# blackfin_f_power.net
KiCad netlist of a schematic drawn in Altium Designer
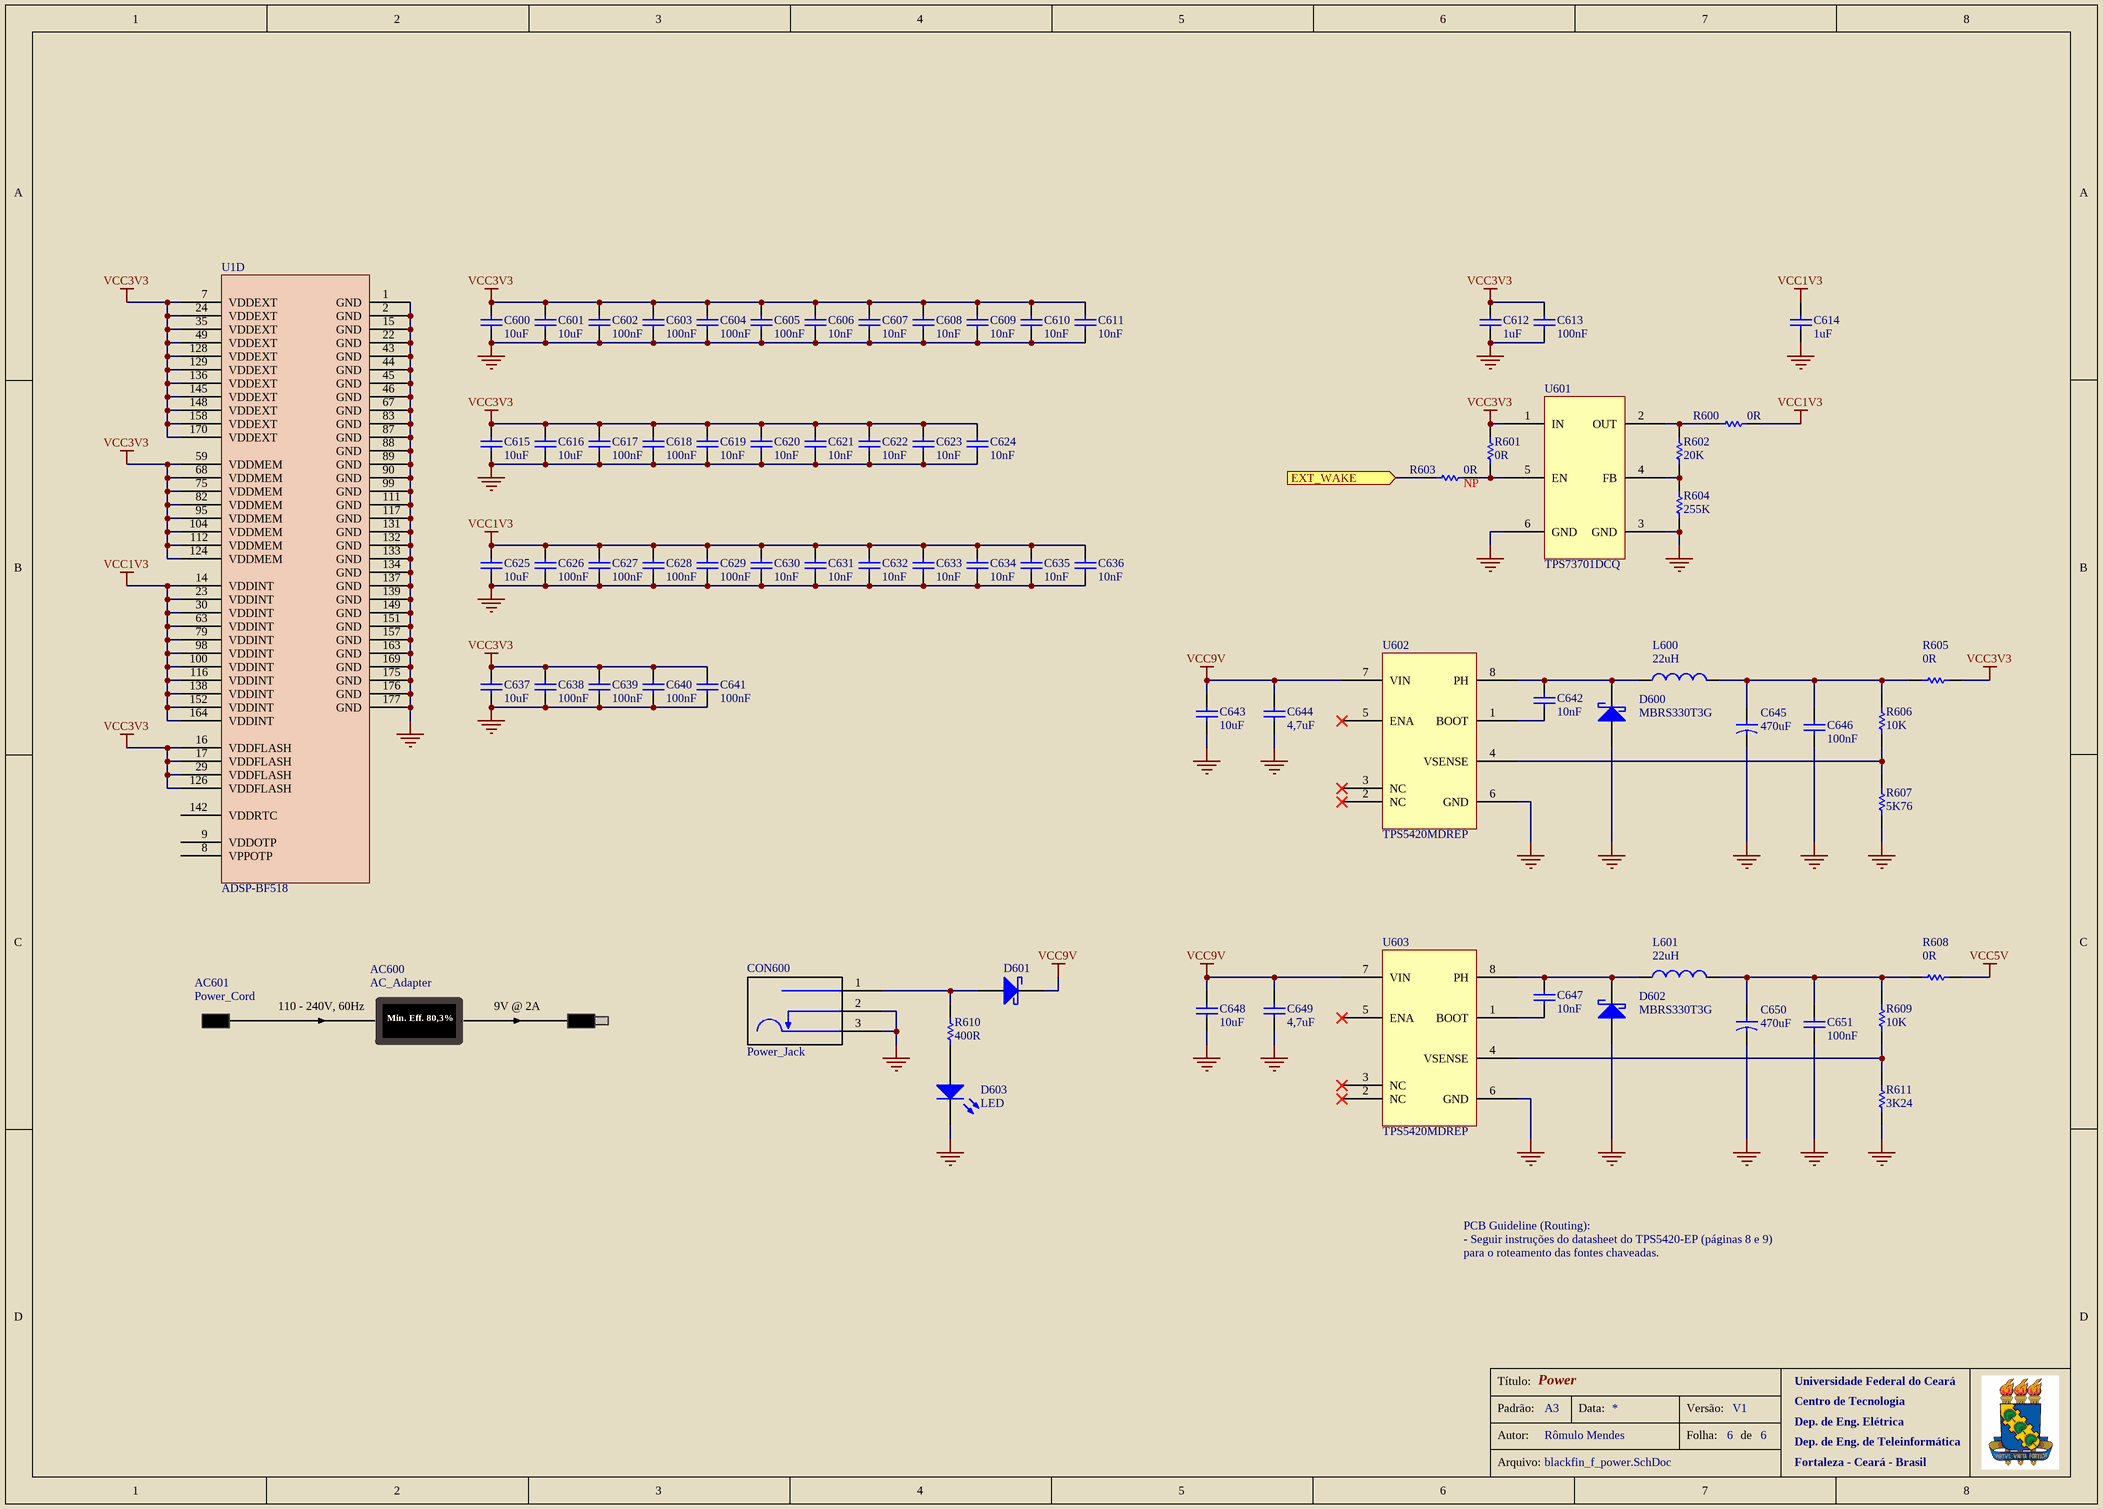
[diagram p0: blackfin_f_power.SchDoc]

(export (version "E")
  (design (tool "Eeschema 10.0.6"))
  (components
    (comp (ref "AC600")
      (value "AC_Adapter")
      (fields
        (field (name "EVENDORPART#") "552-PSA-A18U-090")
        (field (name "PART#") "PSAA18U-090-R")
        (field (name "MANUFACTURER") "Phihong")
      )
      (libsource (lib "blackfin_schlib") (part "AC_Adapter"))
    )
    (comp (ref "AC601")
      (value "Power_Cord")
      (fields
        (field (name "EVENDORPART#") "693-6009.1315")
        (field (name "PART#") "6009.1315")
        (field (name "MANUFACTURER") "Schurter")
      )
      (libsource (lib "blackfin_schlib") (part "Power_Cord"))
    )
    (comp (ref "C600")
      (value "10uF")
      (footprint "blackfin_pcblib:C_0805")
      (fields
        (field (name "EVENDORPART#") "810-C2012Y5V1C106Z")
        (field (name "MANUFACTURER") "TDK")
        (field (name "PART#") "C2012Y5V1C106Z")
      )
      (libsource (lib "blackfin_schlib") (part "Capacitor"))
    )
    (comp (ref "C601")
      (value "10uF")
      (footprint "blackfin_pcblib:C_0805")
      (fields
        (field (name "EVENDORPART#") "810-C2012Y5V1C106Z")
        (field (name "MANUFACTURER") "TDK")
        (field (name "PART#") "C2012Y5V1C106Z")
      )
      (libsource (lib "blackfin_schlib") (part "Capacitor"))
    )
    (comp (ref "C602")
      (value "100nF")
      (footprint "blackfin_pcblib:C_0603")
      (fields
        (field (name "EVENDORPART#") "81-GRM188R71E104KA01")
        (field (name "MANUFACTURER") "Murata")
        (field (name "PART#") "GRM188R71E104KA01J")
      )
      (libsource (lib "blackfin_schlib") (part "Capacitor"))
    )
    (comp (ref "C603")
      (value "100nF")
      (footprint "blackfin_pcblib:C_0603")
      (fields
        (field (name "EVENDORPART#") "81-GRM188R71E104KA01")
        (field (name "MANUFACTURER") "Murata")
        (field (name "PART#") "GRM188R71E104KA01J")
      )
      (libsource (lib "blackfin_schlib") (part "Capacitor"))
    )
    (comp (ref "C604")
      (value "100nF")
      (footprint "blackfin_pcblib:C_0603")
      (fields
        (field (name "EVENDORPART#") "81-GRM188R71E104KA01")
        (field (name "MANUFACTURER") "Murata")
        (field (name "PART#") "GRM188R71E104KA01J")
      )
      (libsource (lib "blackfin_schlib") (part "Capacitor"))
    )
    (comp (ref "C605")
      (value "100nF")
      (footprint "blackfin_pcblib:C_0603")
      (fields
        (field (name "EVENDORPART#") "81-GRM188R71E104KA01")
        (field (name "MANUFACTURER") "Murata")
        (field (name "PART#") "GRM188R71E104KA01J")
      )
      (libsource (lib "blackfin_schlib") (part "Capacitor"))
    )
    (comp (ref "C606")
      (value "10nF")
      (footprint "blackfin_pcblib:C_0603")
      (fields
        (field (name "EVENDORPART#") "77-VJ0603Y103KXAPBC")
        (field (name "MANUFACTURER") "Vishay/Vitramon")
        (field (name "PART#") "VJ0603Y103KXAPW1BC")
      )
      (libsource (lib "blackfin_schlib") (part "Capacitor"))
    )
    (comp (ref "C607")
      (value "10nF")
      (footprint "blackfin_pcblib:C_0603")
      (fields
        (field (name "EVENDORPART#") "77-VJ0603Y103KXAPBC")
        (field (name "MANUFACTURER") "Vishay/Vitramon")
        (field (name "PART#") "VJ0603Y103KXAPW1BC")
      )
      (libsource (lib "blackfin_schlib") (part "Capacitor"))
    )
    (comp (ref "C608")
      (value "10nF")
      (footprint "blackfin_pcblib:C_0603")
      (fields
        (field (name "EVENDORPART#") "77-VJ0603Y103KXAPBC")
        (field (name "MANUFACTURER") "Vishay/Vitramon")
        (field (name "PART#") "VJ0603Y103KXAPW1BC")
      )
      (libsource (lib "blackfin_schlib") (part "Capacitor"))
    )
    (comp (ref "C609")
      (value "10nF")
      (footprint "blackfin_pcblib:C_0603")
      (fields
        (field (name "EVENDORPART#") "77-VJ0603Y103KXAPBC")
        (field (name "MANUFACTURER") "Vishay/Vitramon")
        (field (name "PART#") "VJ0603Y103KXAPW1BC")
      )
      (libsource (lib "blackfin_schlib") (part "Capacitor"))
    )
    (comp (ref "C610")
      (value "10nF")
      (footprint "blackfin_pcblib:C_0603")
      (fields
        (field (name "EVENDORPART#") "77-VJ0603Y103KXAPBC")
        (field (name "MANUFACTURER") "Vishay/Vitramon")
        (field (name "PART#") "VJ0603Y103KXAPW1BC")
      )
      (libsource (lib "blackfin_schlib") (part "Capacitor"))
    )
    (comp (ref "C611")
      (value "10nF")
      (footprint "blackfin_pcblib:C_0603")
      (fields
        (field (name "EVENDORPART#") "77-VJ0603Y103KXAPBC")
        (field (name "MANUFACTURER") "Vishay/Vitramon")
        (field (name "PART#") "VJ0603Y103KXAPW1BC")
      )
      (libsource (lib "blackfin_schlib") (part "Capacitor"))
    )
    (comp (ref "C612")
      (value "1uF")
      (footprint "blackfin_pcblib:C_0603")
      (fields
        (field (name "EVENDORPART#") "81-GRM188F51E105ZA12")
        (field (name "MANUFACTURER") "Murata")
        (field (name "PART#") "GRM188F51E105ZA12D")
      )
      (libsource (lib "blackfin_schlib") (part "Capacitor"))
    )
    (comp (ref "C613")
      (value "100nF")
      (footprint "blackfin_pcblib:C_0603")
      (fields
        (field (name "EVENDORPART#") "81-GRM188R71E104KA01")
        (field (name "MANUFACTURER") "Murata")
        (field (name "PART#") "GRM188R71E104KA01J")
      )
      (libsource (lib "blackfin_schlib") (part "Capacitor"))
    )
    (comp (ref "C614")
      (value "1uF")
      (footprint "blackfin_pcblib:C_0603")
      (fields
        (field (name "EVENDORPART#") "81-GRM188F51E105ZA12")
        (field (name "MANUFACTURER") "Murata")
        (field (name "PART#") "GRM188F51E105ZA12D")
      )
      (libsource (lib "blackfin_schlib") (part "Capacitor"))
    )
    (comp (ref "C615")
      (value "10uF")
      (footprint "blackfin_pcblib:C_0805")
      (fields
        (field (name "EVENDORPART#") "810-C2012Y5V1C106Z")
        (field (name "MANUFACTURER") "TDK")
        (field (name "PART#") "C2012Y5V1C106Z")
      )
      (libsource (lib "blackfin_schlib") (part "Capacitor"))
    )
    (comp (ref "C616")
      (value "10uF")
      (footprint "blackfin_pcblib:C_0805")
      (fields
        (field (name "EVENDORPART#") "810-C2012Y5V1C106Z")
        (field (name "MANUFACTURER") "TDK")
        (field (name "PART#") "C2012Y5V1C106Z")
      )
      (libsource (lib "blackfin_schlib") (part "Capacitor"))
    )
    (comp (ref "C617")
      (value "100nF")
      (footprint "blackfin_pcblib:C_0603")
      (fields
        (field (name "EVENDORPART#") "81-GRM188R71E104KA01")
        (field (name "MANUFACTURER") "Murata")
        (field (name "PART#") "GRM188R71E104KA01J")
      )
      (libsource (lib "blackfin_schlib") (part "Capacitor"))
    )
    (comp (ref "C618")
      (value "100nF")
      (footprint "blackfin_pcblib:C_0603")
      (fields
        (field (name "EVENDORPART#") "81-GRM188R71E104KA01")
        (field (name "MANUFACTURER") "Murata")
        (field (name "PART#") "GRM188R71E104KA01J")
      )
      (libsource (lib "blackfin_schlib") (part "Capacitor"))
    )
    (comp (ref "C619")
      (value "10nF")
      (footprint "blackfin_pcblib:C_0603")
      (fields
        (field (name "EVENDORPART#") "77-VJ0603Y103KXAPBC")
        (field (name "MANUFACTURER") "Vishay/Vitramon")
        (field (name "PART#") "VJ0603Y103KXAPW1BC")
      )
      (libsource (lib "blackfin_schlib") (part "Capacitor"))
    )
    (comp (ref "C620")
      (value "10nF")
      (footprint "blackfin_pcblib:C_0603")
      (fields
        (field (name "EVENDORPART#") "77-VJ0603Y103KXAPBC")
        (field (name "MANUFACTURER") "Vishay/Vitramon")
        (field (name "PART#") "VJ0603Y103KXAPW1BC")
      )
      (libsource (lib "blackfin_schlib") (part "Capacitor"))
    )
    (comp (ref "C621")
      (value "10nF")
      (footprint "blackfin_pcblib:C_0603")
      (fields
        (field (name "EVENDORPART#") "77-VJ0603Y103KXAPBC")
        (field (name "MANUFACTURER") "Vishay/Vitramon")
        (field (name "PART#") "VJ0603Y103KXAPW1BC")
      )
      (libsource (lib "blackfin_schlib") (part "Capacitor"))
    )
    (comp (ref "C622")
      (value "10nF")
      (footprint "blackfin_pcblib:C_0603")
      (fields
        (field (name "EVENDORPART#") "77-VJ0603Y103KXAPBC")
        (field (name "MANUFACTURER") "Vishay/Vitramon")
        (field (name "PART#") "VJ0603Y103KXAPW1BC")
      )
      (libsource (lib "blackfin_schlib") (part "Capacitor"))
    )
    (comp (ref "C623")
      (value "10nF")
      (footprint "blackfin_pcblib:C_0603")
      (fields
        (field (name "EVENDORPART#") "77-VJ0603Y103KXAPBC")
        (field (name "MANUFACTURER") "Vishay/Vitramon")
        (field (name "PART#") "VJ0603Y103KXAPW1BC")
      )
      (libsource (lib "blackfin_schlib") (part "Capacitor"))
    )
    (comp (ref "C624")
      (value "10nF")
      (footprint "blackfin_pcblib:C_0603")
      (fields
        (field (name "EVENDORPART#") "77-VJ0603Y103KXAPBC")
        (field (name "MANUFACTURER") "Vishay/Vitramon")
        (field (name "PART#") "VJ0603Y103KXAPW1BC")
      )
      (libsource (lib "blackfin_schlib") (part "Capacitor"))
    )
    (comp (ref "C625")
      (value "10uF")
      (footprint "blackfin_pcblib:C_0805")
      (fields
        (field (name "EVENDORPART#") "810-C2012Y5V1C106Z")
        (field (name "MANUFACTURER") "TDK")
        (field (name "PART#") "C2012Y5V1C106Z")
      )
      (libsource (lib "blackfin_schlib") (part "Capacitor"))
    )
    (comp (ref "C626")
      (value "100nF")
      (footprint "blackfin_pcblib:C_0603")
      (fields
        (field (name "EVENDORPART#") "81-GRM188R71E104KA01")
        (field (name "MANUFACTURER") "Murata")
        (field (name "PART#") "GRM188R71E104KA01J")
      )
      (libsource (lib "blackfin_schlib") (part "Capacitor"))
    )
    (comp (ref "C627")
      (value "100nF")
      (footprint "blackfin_pcblib:C_0603")
      (fields
        (field (name "EVENDORPART#") "81-GRM188R71E104KA01")
        (field (name "MANUFACTURER") "Murata")
        (field (name "PART#") "GRM188R71E104KA01J")
      )
      (libsource (lib "blackfin_schlib") (part "Capacitor"))
    )
    (comp (ref "C628")
      (value "100nF")
      (footprint "blackfin_pcblib:C_0603")
      (fields
        (field (name "EVENDORPART#") "81-GRM188R71E104KA01")
        (field (name "MANUFACTURER") "Murata")
        (field (name "PART#") "GRM188R71E104KA01J")
      )
      (libsource (lib "blackfin_schlib") (part "Capacitor"))
    )
    (comp (ref "C629")
      (value "100nF")
      (footprint "blackfin_pcblib:C_0603")
      (fields
        (field (name "EVENDORPART#") "81-GRM188R71E104KA01")
        (field (name "MANUFACTURER") "Murata")
        (field (name "PART#") "GRM188R71E104KA01J")
      )
      (libsource (lib "blackfin_schlib") (part "Capacitor"))
    )
    (comp (ref "C630")
      (value "10nF")
      (footprint "blackfin_pcblib:C_0603")
      (fields
        (field (name "EVENDORPART#") "77-VJ0603Y103KXAPBC")
        (field (name "MANUFACTURER") "Vishay/Vitramon")
        (field (name "PART#") "VJ0603Y103KXAPW1BC")
      )
      (libsource (lib "blackfin_schlib") (part "Capacitor"))
    )
    (comp (ref "C631")
      (value "10nF")
      (footprint "blackfin_pcblib:C_0603")
      (fields
        (field (name "EVENDORPART#") "77-VJ0603Y103KXAPBC")
        (field (name "MANUFACTURER") "Vishay/Vitramon")
        (field (name "PART#") "VJ0603Y103KXAPW1BC")
      )
      (libsource (lib "blackfin_schlib") (part "Capacitor"))
    )
    (comp (ref "C632")
      (value "10nF")
      (footprint "blackfin_pcblib:C_0603")
      (fields
        (field (name "EVENDORPART#") "77-VJ0603Y103KXAPBC")
        (field (name "MANUFACTURER") "Vishay/Vitramon")
        (field (name "PART#") "VJ0603Y103KXAPW1BC")
      )
      (libsource (lib "blackfin_schlib") (part "Capacitor"))
    )
    (comp (ref "C633")
      (value "10nF")
      (footprint "blackfin_pcblib:C_0603")
      (fields
        (field (name "EVENDORPART#") "77-VJ0603Y103KXAPBC")
        (field (name "MANUFACTURER") "Vishay/Vitramon")
        (field (name "PART#") "VJ0603Y103KXAPW1BC")
      )
      (libsource (lib "blackfin_schlib") (part "Capacitor"))
    )
    (comp (ref "C634")
      (value "10nF")
      (footprint "blackfin_pcblib:C_0603")
      (fields
        (field (name "EVENDORPART#") "77-VJ0603Y103KXAPBC")
        (field (name "MANUFACTURER") "Vishay/Vitramon")
        (field (name "PART#") "VJ0603Y103KXAPW1BC")
      )
      (libsource (lib "blackfin_schlib") (part "Capacitor"))
    )
    (comp (ref "C635")
      (value "10nF")
      (footprint "blackfin_pcblib:C_0603")
      (fields
        (field (name "EVENDORPART#") "77-VJ0603Y103KXAPBC")
        (field (name "MANUFACTURER") "Vishay/Vitramon")
        (field (name "PART#") "VJ0603Y103KXAPW1BC")
      )
      (libsource (lib "blackfin_schlib") (part "Capacitor"))
    )
    (comp (ref "C636")
      (value "10nF")
      (footprint "blackfin_pcblib:C_0603")
      (fields
        (field (name "EVENDORPART#") "77-VJ0603Y103KXAPBC")
        (field (name "MANUFACTURER") "Vishay/Vitramon")
        (field (name "PART#") "VJ0603Y103KXAPW1BC")
      )
      (libsource (lib "blackfin_schlib") (part "Capacitor"))
    )
    (comp (ref "C637")
      (value "10uF")
      (footprint "blackfin_pcblib:C_0805")
      (fields
        (field (name "EVENDORPART#") "810-C2012Y5V1C106Z")
        (field (name "MANUFACTURER") "TDK")
        (field (name "PART#") "C2012Y5V1C106Z")
      )
      (libsource (lib "blackfin_schlib") (part "Capacitor"))
    )
    (comp (ref "C638")
      (value "100nF")
      (footprint "blackfin_pcblib:C_0603")
      (fields
        (field (name "EVENDORPART#") "81-GRM188R71E104KA01")
        (field (name "MANUFACTURER") "Murata")
        (field (name "PART#") "GRM188R71E104KA01J")
      )
      (libsource (lib "blackfin_schlib") (part "Capacitor"))
    )
    (comp (ref "C639")
      (value "100nF")
      (footprint "blackfin_pcblib:C_0603")
      (fields
        (field (name "EVENDORPART#") "81-GRM188R71E104KA01")
        (field (name "MANUFACTURER") "Murata")
        (field (name "PART#") "GRM188R71E104KA01J")
      )
      (libsource (lib "blackfin_schlib") (part "Capacitor"))
    )
    (comp (ref "C640")
      (value "100nF")
      (footprint "blackfin_pcblib:C_0603")
      (fields
        (field (name "EVENDORPART#") "81-GRM188R71E104KA01")
        (field (name "MANUFACTURER") "Murata")
        (field (name "PART#") "GRM188R71E104KA01J")
      )
      (libsource (lib "blackfin_schlib") (part "Capacitor"))
    )
    (comp (ref "C641")
      (value "100nF")
      (footprint "blackfin_pcblib:C_0603")
      (fields
        (field (name "EVENDORPART#") "81-GRM188R71E104KA01")
        (field (name "MANUFACTURER") "Murata")
        (field (name "PART#") "GRM188R71E104KA01J")
      )
      (libsource (lib "blackfin_schlib") (part "Capacitor"))
    )
    (comp (ref "C642")
      (value "10nF")
      (footprint "blackfin_pcblib:C_0805")
      (fields
        (field (name "EVENDORPART#") "81-GRM216R71H103JA1D")
        (field (name "MANUFACTURER") "Murata")
        (field (name "PART#") "GRM216R71H103JA01D")
      )
      (libsource (lib "blackfin_schlib") (part "Capacitor"))
    )
    (comp (ref "C643")
      (value "10uF")
      (footprint "blackfin_pcblib:C_0805")
      (fields
        (field (name "EVENDORPART#") "810-C2012X5R1C106M")
        (field (name "MANUFACTURER") "TDK")
        (field (name "PART#") "C2012X5R1C106M")
      )
      (libsource (lib "blackfin_schlib") (part "Capacitor"))
    )
    (comp (ref "C644")
      (value "4,7uF")
      (footprint "blackfin_pcblib:C_0805")
      (fields
        (field (name "EVENDORPART#") "81-GRM21BR61C475KA8L")
        (field (name "MANUFACTURER") "Murata")
        (field (name "PART#") "GRM21BR61C475KA88L")
      )
      (libsource (lib "blackfin_schlib") (part "Capacitor"))
    )
    (comp (ref "C645")
      (value "470uF")
      (footprint "blackfin_pcblib:C_Case_Y")
      (fields
        (field (name "EVENDORPART#") "80-T520Y477M6ATE15")
        (field (name "PART#") "T520Y477M006ATE015")
        (field (name "MANUFACTURER") "Kemet")
      )
      (libsource (lib "blackfin_schlib") (part "Capacitor_Pol"))
    )
    (comp (ref "C646")
      (value "100nF")
      (footprint "blackfin_pcblib:C_0603")
      (fields
        (field (name "EVENDORPART#") "81-GRM188R71E104KA01")
        (field (name "MANUFACTURER") "Murata")
        (field (name "PART#") "GRM188R71E104KA01J")
      )
      (libsource (lib "blackfin_schlib") (part "Capacitor"))
    )
    (comp (ref "C647")
      (value "10nF")
      (footprint "blackfin_pcblib:C_0805")
      (fields
        (field (name "EVENDORPART#") "81-GRM216R71H103JA1D")
        (field (name "MANUFACTURER") "Murata")
        (field (name "PART#") "GRM216R71H103JA01D")
      )
      (libsource (lib "blackfin_schlib") (part "Capacitor"))
    )
    (comp (ref "C648")
      (value "10uF")
      (footprint "blackfin_pcblib:C_0805")
      (fields
        (field (name "EVENDORPART#") "810-C2012X5R1C106M")
        (field (name "MANUFACTURER") "TDK")
        (field (name "PART#") "C2012X5R1C106M")
      )
      (libsource (lib "blackfin_schlib") (part "Capacitor"))
    )
    (comp (ref "C649")
      (value "4,7uF")
      (footprint "blackfin_pcblib:C_0805")
      (fields
        (field (name "EVENDORPART#") "81-GRM21BR61C475KA8L")
        (field (name "MANUFACTURER") "Murata")
        (field (name "PART#") "GRM21BR61C475KA88L")
      )
      (libsource (lib "blackfin_schlib") (part "Capacitor"))
    )
    (comp (ref "C650")
      (value "470uF")
      (footprint "blackfin_pcblib:C_Case_Y")
      (fields
        (field (name "EVENDORPART#") "80-T520Y477M6ATE15")
        (field (name "PART#") "T520Y477M006ATE015")
        (field (name "MANUFACTURER") "Kemet")
      )
      (libsource (lib "blackfin_schlib") (part "Capacitor_Pol"))
    )
    (comp (ref "C651")
      (value "100nF")
      (footprint "blackfin_pcblib:C_0603")
      (fields
        (field (name "EVENDORPART#") "81-GRM188R71E104KA01")
        (field (name "MANUFACTURER") "Murata")
        (field (name "PART#") "GRM188R71E104KA01J")
      )
      (libsource (lib "blackfin_schlib") (part "Capacitor"))
    )
    (comp (ref "CON600")
      (value "Power_Jack")
      (footprint "blackfin_pcblib:Power_Jack")
      (fields (field (name "EVENDORPART#") "163-179PH-EX") (field (name "MANUFACTURER") "Kobiconn"))
      (libsource (lib "blackfin_schlib") (part "Power_Jack"))
    )
    (comp (ref "D600")
      (value "MBRS330T3G")
      (footprint "blackfin_pcblib:Case_430")
      (fields (field (name "EVENDORPART#") "863-MBRS330T3G") (field (name "MANUFACTURER") "ON Semiconductor"))
      (libsource (lib "blackfin_schlib") (part "Schottky_Diode"))
    )
    (comp (ref "D601")
      (value "Schottky_Diode")
      (footprint "blackfin_pcblib:Case_430")
      (fields
        (field (name "EVENDORPART#") "863-MBRS330T3G")
        (field (name "PART#") "MBRS330T3G")
        (field (name "MANUFACTURER") "ON Semiconductor")
      )
      (libsource (lib "blackfin_schlib") (part "Schottky_Diode"))
    )
    (comp (ref "D602")
      (value "MBRS330T3G")
      (footprint "blackfin_pcblib:Case_430")
      (fields (field (name "EVENDORPART#") "863-MBRS330T3G") (field (name "MANUFACTURER") "ON Semiconductor"))
      (libsource (lib "blackfin_schlib") (part "Schottky_Diode"))
    )
    (comp (ref "D603")
      (value "LED")
      (footprint "blackfin_pcblib:LED_0603")
      (description "Red LED")
      (fields (field (name "EVENDORPART#") "638-QTLP600C2TR") (field (name "MANUFACTURER") "Everlight"))
      (libsource (lib "blackfin_schlib") (part "LED"))
    )
    (comp (ref "L600")
      (value "22uH")
      (footprint "blackfin_pcblib:Inductor_22uH")
      (fields
        (field (name "EVENDORPART#") "710-744066220")
        (field (name "MANUFACTURER") "Wurth Electronics")
        (field (name "PART#") "744066220")
      )
      (libsource (lib "blackfin_schlib") (part "Inductor"))
    )
    (comp (ref "L601")
      (value "22uH")
      (footprint "blackfin_pcblib:Inductor_22uH")
      (fields
        (field (name "EVENDORPART#") "710-744066220")
        (field (name "MANUFACTURER") "Wurth Electronics")
        (field (name "PART#") "744066220")
      )
      (libsource (lib "blackfin_schlib") (part "Inductor"))
    )
    (comp (ref "R600")
      (value "0R")
      (footprint "blackfin_pcblib:R_0603")
      (fields
        (field (name "EVENDORPART#") "71-CRCW06030000Z0EB")
        (field (name "PART#") "CRCW06030000Z0EB")
        (field (name "MANUFACTURER") "Vishay/Dale")
      )
      (libsource (lib "blackfin_schlib") (part "Resistor"))
    )
    (comp (ref "R601")
      (value "0R")
      (footprint "blackfin_pcblib:R_0603")
      (fields
        (field (name "EVENDORPART#") "71-CRCW06030000Z0EB")
        (field (name "PART#") "CRCW06030000Z0EB")
        (field (name "MANUFACTURER") "Vishay/Dale")
      )
      (libsource (lib "blackfin_schlib") (part "Resistor"))
    )
    (comp (ref "R602")
      (value "20K")
      (footprint "blackfin_pcblib:R_0603")
      (fields
        (field (name "EVENDORPART#") "71-CRCW0603J-20K-E3")
        (field (name "PART#") "CRCW060320K0JNEA")
        (field (name "MANUFACTURER") "Vishay/Dale")
      )
      (libsource (lib "blackfin_schlib") (part "Resistor"))
    )
    (comp (ref "R603")
      (value "0R")
      (footprint "blackfin_pcblib:R_0603")
      (fields
        (field (name "EVENDORPART#") "71-CRCW06030000Z0EB")
        (field (name "PART#") "CRCW06030000Z0EB")
        (field (name "MANUFACTURER") "Vishay/Dale")
      )
      (libsource (lib "blackfin_schlib") (part "Resistor"))
    )
    (comp (ref "R604")
      (value "255K")
      (footprint "blackfin_pcblib:R_0603")
      (fields
        (field (name "EVENDORPART#") "71-CRCW0603-255K-E3")
        (field (name "PART#") "CRCW0603255KFKEA")
        (field (name "MANUFACTURER") "Vishay/Dale")
      )
      (libsource (lib "blackfin_schlib") (part "Resistor"))
    )
    (comp (ref "R605")
      (value "0R")
      (footprint "blackfin_pcblib:R_2512")
      (fields
        (field (name "EVENDORPART#") "71-CRCW2512-0-E3")
        (field (name "PART#") "CRCW25120000Z0EG")
        (field (name "MANUFACTURER") "Vishay/Dale")
      )
      (libsource (lib "blackfin_schlib") (part "Resistor"))
    )
    (comp (ref "R606")
      (value "10K")
      (footprint "blackfin_pcblib:R_0603")
      (fields
        (field (name "EVENDORPART#") "71-CRCW0603-10K-E3")
        (field (name "PART#") "CRCW060310K0FKEA")
        (field (name "MANUFACTURER") "Vishay/Dale")
      )
      (libsource (lib "blackfin_schlib") (part "Resistor"))
    )
    (comp (ref "R607")
      (value "5K76")
      (footprint "blackfin_pcblib:R_0603")
      (fields
        (field (name "EVENDORPART#") "660-RK73H1JTTDD5761F")
        (field (name "PART#") "RK73H1JTTDD5761F")
        (field (name "MANUFACTURER") "KOA Speer")
      )
      (libsource (lib "blackfin_schlib") (part "Resistor"))
    )
    (comp (ref "R608")
      (value "0R")
      (footprint "blackfin_pcblib:R_2512")
      (fields
        (field (name "EVENDORPART#") "71-CRCW2512-0-E3")
        (field (name "PART#") "CRCW25120000Z0EG")
        (field (name "MANUFACTURER") "Vishay/Dale")
      )
      (libsource (lib "blackfin_schlib") (part "Resistor"))
    )
    (comp (ref "R609")
      (value "10K")
      (footprint "blackfin_pcblib:R_0603")
      (fields
        (field (name "EVENDORPART#") "71-CRCW0603-10K-E3")
        (field (name "PART#") "CRCW060310K0FKEA")
        (field (name "MANUFACTURER") "Vishay/Dale")
      )
      (libsource (lib "blackfin_schlib") (part "Resistor"))
    )
    (comp (ref "R610")
      (value "400R")
      (footprint "blackfin_pcblib:R_1206")
      (fields
        (field (name "EVENDORPART#") "71-CRCW1206390RJNEB")
        (field (name "PART#") "CRCW1206390RJNEB")
        (field (name "MANUFACTURER") "Vishay/Dale")
      )
      (libsource (lib "blackfin_schlib") (part "Resistor"))
    )
    (comp (ref "R611")
      (value "3K24")
      (footprint "blackfin_pcblib:R_0603")
      (fields
        (field (name "EVENDORPART#") "71-CRCW0603-3.24K-E3")
        (field (name "PART#") "CRCW06033K24FKEA")
        (field (name "MANUFACTURER") "Vishay/Dale")
      )
      (libsource (lib "blackfin_schlib") (part "Resistor"))
    )
    (comp (ref "U1")
      (value "ADSP-BF518")
      (footprint "blackfin_pcblib:LQFP-176")
      (fields (field (name "EVENDORPART#") "ADSP-BF518BSWZ-4") (field (name "MANUFACTURER") "Analog Devices"))
      (libsource (lib "blackfin_schlib") (part "ADSP-BF518"))
    )
    (comp (ref "U601")
      (value "TPS73701DCQ")
      (footprint "blackfin_pcblib:SOT-223")
      (fields
        (field (name "EVENDORPART#") "595-TPS73701DCQ")
        (field (name "MANUFACTURER") "Texas Instruments")
      )
      (libsource (lib "blackfin_schlib") (part "TPS73701DCQ"))
    )
    (comp (ref "U602")
      (value "TPS5420MDREP")
      (footprint "blackfin_pcblib:SOIC-8 (TPS5420MDREP)")
      (fields
        (field (name "EVENDORPART#") "595-TPS5420MDREP")
        (field (name "MANUFACTURER") "Texas Instruments")
      )
      (libsource (lib "blackfin_schlib") (part "TPS5420MDREP"))
    )
    (comp (ref "U603")
      (value "TPS5420MDREP")
      (footprint "blackfin_pcblib:SOIC-8 (TPS5420MDREP)")
      (fields
        (field (name "EVENDORPART#") "595-TPS5420MDREP")
        (field (name "MANUFACTURER") "Texas Instruments")
      )
      (libsource (lib "blackfin_schlib") (part "TPS5420MDREP"))
    )
  )
  (nets
    (net (code "1") (name "/EXT_WAKE") (class "Default")
      (node (ref "R603") (pin "1") (pinfunction "1_1") (pintype "passive"))
    )
    (net (code "2") (name "GND") (class "Default")
      (node (ref "C600") (pin "1") (pinfunction "1_1") (pintype "passive"))
      (node (ref "C601") (pin "1") (pinfunction "1_1") (pintype "passive"))
      (node (ref "C602") (pin "1") (pinfunction "1_1") (pintype "passive"))
      (node (ref "C603") (pin "1") (pinfunction "1_1") (pintype "passive"))
      (node (ref "C604") (pin "1") (pinfunction "1_1") (pintype "passive"))
      (node (ref "C605") (pin "1") (pinfunction "1_1") (pintype "passive"))
      (node (ref "C606") (pin "1") (pinfunction "1_1") (pintype "passive"))
      (node (ref "C607") (pin "1") (pinfunction "1_1") (pintype "passive"))
      (node (ref "C608") (pin "1") (pinfunction "1_1") (pintype "passive"))
      (node (ref "C609") (pin "1") (pinfunction "1_1") (pintype "passive"))
      (node (ref "C610") (pin "1") (pinfunction "1_1") (pintype "passive"))
      (node (ref "C611") (pin "1") (pinfunction "1_1") (pintype "passive"))
      (node (ref "C612") (pin "1") (pinfunction "1_1") (pintype "passive"))
      (node (ref "C613") (pin "1") (pinfunction "1_1") (pintype "passive"))
      (node (ref "C614") (pin "1") (pinfunction "1_1") (pintype "passive"))
      (node (ref "C615") (pin "1") (pinfunction "1_1") (pintype "passive"))
      (node (ref "C616") (pin "1") (pinfunction "1_1") (pintype "passive"))
      (node (ref "C617") (pin "1") (pinfunction "1_1") (pintype "passive"))
      (node (ref "C618") (pin "1") (pinfunction "1_1") (pintype "passive"))
      (node (ref "C619") (pin "1") (pinfunction "1_1") (pintype "passive"))
      (node (ref "C620") (pin "1") (pinfunction "1_1") (pintype "passive"))
      (node (ref "C621") (pin "1") (pinfunction "1_1") (pintype "passive"))
      (node (ref "C622") (pin "1") (pinfunction "1_1") (pintype "passive"))
      (node (ref "C623") (pin "1") (pinfunction "1_1") (pintype "passive"))
      (node (ref "C624") (pin "1") (pinfunction "1_1") (pintype "passive"))
      (node (ref "C625") (pin "1") (pinfunction "1_1") (pintype "passive"))
      (node (ref "C626") (pin "1") (pinfunction "1_1") (pintype "passive"))
      (node (ref "C627") (pin "1") (pinfunction "1_1") (pintype "passive"))
      (node (ref "C628") (pin "1") (pinfunction "1_1") (pintype "passive"))
      (node (ref "C629") (pin "1") (pinfunction "1_1") (pintype "passive"))
      (node (ref "C630") (pin "1") (pinfunction "1_1") (pintype "passive"))
      (node (ref "C631") (pin "1") (pinfunction "1_1") (pintype "passive"))
      (node (ref "C632") (pin "1") (pinfunction "1_1") (pintype "passive"))
      (node (ref "C633") (pin "1") (pinfunction "1_1") (pintype "passive"))
      (node (ref "C634") (pin "1") (pinfunction "1_1") (pintype "passive"))
      (node (ref "C635") (pin "1") (pinfunction "1_1") (pintype "passive"))
      (node (ref "C636") (pin "1") (pinfunction "1_1") (pintype "passive"))
      (node (ref "C637") (pin "1") (pinfunction "1_1") (pintype "passive"))
      (node (ref "C638") (pin "1") (pinfunction "1_1") (pintype "passive"))
      (node (ref "C639") (pin "1") (pinfunction "1_1") (pintype "passive"))
      (node (ref "C640") (pin "1") (pinfunction "1_1") (pintype "passive"))
      (node (ref "C641") (pin "1") (pinfunction "1_1") (pintype "passive"))
      (node (ref "C643") (pin "1") (pinfunction "1_1") (pintype "passive"))
      (node (ref "C644") (pin "1") (pinfunction "1_1") (pintype "passive"))
      (node (ref "C645") (pin "2") (pinfunction "2_2") (pintype "passive"))
      (node (ref "C646") (pin "1") (pinfunction "1_1") (pintype "passive"))
      (node (ref "C648") (pin "1") (pinfunction "1_1") (pintype "passive"))
      (node (ref "C649") (pin "1") (pinfunction "1_1") (pintype "passive"))
      (node (ref "C650") (pin "2") (pinfunction "2_2") (pintype "passive"))
      (node (ref "C651") (pin "1") (pinfunction "1_1") (pintype "passive"))
      (node (ref "CON600") (pin "2") (pinfunction "2_2") (pintype "passive"))
      (node (ref "CON600") (pin "3") (pinfunction "3_3") (pintype "passive"))
      (node (ref "D600") (pin "1") (pinfunction "A_1") (pintype "passive"))
      (node (ref "D602") (pin "1") (pinfunction "A_1") (pintype "passive"))
      (node (ref "D603") (pin "2") (pinfunction "K_2") (pintype "passive"))
      (node (ref "R604") (pin "1") (pinfunction "1_1") (pintype "passive"))
      (node (ref "R607") (pin "1") (pinfunction "1_1") (pintype "passive"))
      (node (ref "R611") (pin "1") (pinfunction "1_1") (pintype "passive"))
      (node (ref "U1") (pin "1") (pinfunction "GND_1") (pintype "passive"))
      (node (ref "U1") (pin "111") (pinfunction "GND_111") (pintype "passive"))
      (node (ref "U1") (pin "117") (pinfunction "GND_117") (pintype "passive"))
      (node (ref "U1") (pin "131") (pinfunction "GND_131") (pintype "passive"))
      (node (ref "U1") (pin "132") (pinfunction "GND_132") (pintype "passive"))
      (node (ref "U1") (pin "133") (pinfunction "GND_133") (pintype "passive"))
      (node (ref "U1") (pin "134") (pinfunction "GND_134") (pintype "passive"))
      (node (ref "U1") (pin "137") (pinfunction "GND_137") (pintype "passive"))
      (node (ref "U1") (pin "139") (pinfunction "GND_139") (pintype "passive"))
      (node (ref "U1") (pin "149") (pinfunction "GND_149") (pintype "passive"))
      (node (ref "U1") (pin "15") (pinfunction "GND_15") (pintype "passive"))
      (node (ref "U1") (pin "151") (pinfunction "GND_151") (pintype "passive"))
      (node (ref "U1") (pin "157") (pinfunction "GND_157") (pintype "passive"))
      (node (ref "U1") (pin "163") (pinfunction "GND_163") (pintype "passive"))
      (node (ref "U1") (pin "169") (pinfunction "GND_169") (pintype "passive"))
      (node (ref "U1") (pin "175") (pinfunction "GND_175") (pintype "passive"))
      (node (ref "U1") (pin "176") (pinfunction "GND_176") (pintype "passive"))
      (node (ref "U1") (pin "177") (pinfunction "GND_177") (pintype "passive"))
      (node (ref "U1") (pin "2") (pinfunction "GND_2") (pintype "passive"))
      (node (ref "U1") (pin "22") (pinfunction "GND_22") (pintype "passive"))
      (node (ref "U1") (pin "43") (pinfunction "GND_43") (pintype "passive"))
      (node (ref "U1") (pin "44") (pinfunction "GND_44") (pintype "passive"))
      (node (ref "U1") (pin "45") (pinfunction "GND_45") (pintype "passive"))
      (node (ref "U1") (pin "46") (pinfunction "GND_46") (pintype "passive"))
      (node (ref "U1") (pin "67") (pinfunction "GND_67") (pintype "passive"))
      (node (ref "U1") (pin "83") (pinfunction "GND_83") (pintype "passive"))
      (node (ref "U1") (pin "87") (pinfunction "GND_87") (pintype "passive"))
      (node (ref "U1") (pin "88") (pinfunction "GND_88") (pintype "passive"))
      (node (ref "U1") (pin "89") (pinfunction "GND_89") (pintype "passive"))
      (node (ref "U1") (pin "90") (pinfunction "GND_90") (pintype "passive"))
      (node (ref "U1") (pin "99") (pinfunction "GND_99") (pintype "passive"))
      (node (ref "U601") (pin "3") (pinfunction "GND_3") (pintype "passive"))
      (node (ref "U601") (pin "6") (pinfunction "GND_6") (pintype "passive"))
      (node (ref "U602") (pin "6") (pinfunction "GND_6") (pintype "passive"))
      (node (ref "U603") (pin "6") (pinfunction "GND_6") (pintype "passive"))
    )
    (net (code "3") (name "Net-(C645-Pad1)") (class "Default")
      (node (ref "C645") (pin "1") (pinfunction "1_1") (pintype "passive"))
      (node (ref "C646") (pin "2") (pinfunction "2_2") (pintype "passive"))
      (node (ref "L600") (pin "2") (pinfunction "2_2") (pintype "passive"))
      (node (ref "R605") (pin "1") (pinfunction "1_1") (pintype "passive"))
      (node (ref "R606") (pin "2") (pinfunction "2_2") (pintype "passive"))
    )
    (net (code "4") (name "Net-(C650-Pad1)") (class "Default")
      (node (ref "C650") (pin "1") (pinfunction "1_1") (pintype "passive"))
      (node (ref "C651") (pin "2") (pinfunction "2_2") (pintype "passive"))
      (node (ref "L601") (pin "2") (pinfunction "2_2") (pintype "passive"))
      (node (ref "R608") (pin "1") (pinfunction "1_1") (pintype "passive"))
      (node (ref "R609") (pin "2") (pinfunction "2_2") (pintype "passive"))
    )
    (net (code "5") (name "Net-(D600-K)") (class "Default")
      (node (ref "C642") (pin "2") (pinfunction "2_2") (pintype "passive"))
      (node (ref "D600") (pin "2") (pinfunction "K_2") (pintype "passive"))
      (node (ref "L600") (pin "1") (pinfunction "1_1") (pintype "passive"))
      (node (ref "U602") (pin "8") (pinfunction "PH_8") (pintype "passive"))
    )
    (net (code "6") (name "Net-(D601-A)") (class "Default")
      (node (ref "CON600") (pin "1") (pinfunction "1_1") (pintype "passive"))
      (node (ref "D601") (pin "1") (pinfunction "A_1") (pintype "passive"))
      (node (ref "R610") (pin "2") (pinfunction "2_2") (pintype "passive"))
    )
    (net (code "7") (name "Net-(D602-K)") (class "Default")
      (node (ref "C647") (pin "2") (pinfunction "2_2") (pintype "passive"))
      (node (ref "D602") (pin "2") (pinfunction "K_2") (pintype "passive"))
      (node (ref "L601") (pin "1") (pinfunction "1_1") (pintype "passive"))
      (node (ref "U603") (pin "8") (pinfunction "PH_8") (pintype "passive"))
    )
    (net (code "8") (name "Net-(D603-A)") (class "Default")
      (node (ref "D603") (pin "1") (pinfunction "A_1") (pintype "passive"))
      (node (ref "R610") (pin "1") (pinfunction "1_1") (pintype "passive"))
    )
    (net (code "9") (name "Net-(U601-EN)") (class "Default")
      (node (ref "R601") (pin "1") (pinfunction "1_1") (pintype "passive"))
      (node (ref "R603") (pin "2") (pinfunction "2_2") (pintype "passive"))
      (node (ref "U601") (pin "5") (pinfunction "EN_5") (pintype "passive"))
    )
    (net (code "10") (name "Net-(U601-FB)") (class "Default")
      (node (ref "R602") (pin "1") (pinfunction "1_1") (pintype "passive"))
      (node (ref "R604") (pin "2") (pinfunction "2_2") (pintype "passive"))
      (node (ref "U601") (pin "4") (pinfunction "FB_4") (pintype "passive"))
    )
    (net (code "11") (name "Net-(U601-OUT)") (class "Default")
      (node (ref "R600") (pin "1") (pinfunction "1_1") (pintype "passive"))
      (node (ref "R602") (pin "2") (pinfunction "2_2") (pintype "passive"))
      (node (ref "U601") (pin "2") (pinfunction "OUT_2") (pintype "passive"))
    )
    (net (code "12") (name "Net-(U602-BOOT)") (class "Default")
      (node (ref "C642") (pin "1") (pinfunction "1_1") (pintype "passive"))
      (node (ref "U602") (pin "1") (pinfunction "BOOT_1") (pintype "passive"))
    )
    (net (code "13") (name "Net-(U602-VSENSE)") (class "Default")
      (node (ref "R606") (pin "1") (pinfunction "1_1") (pintype "passive"))
      (node (ref "R607") (pin "2") (pinfunction "2_2") (pintype "passive"))
      (node (ref "U602") (pin "4") (pinfunction "VSENSE_4") (pintype "passive"))
    )
    (net (code "14") (name "Net-(U603-BOOT)") (class "Default")
      (node (ref "C647") (pin "1") (pinfunction "1_1") (pintype "passive"))
      (node (ref "U603") (pin "1") (pinfunction "BOOT_1") (pintype "passive"))
    )
    (net (code "15") (name "Net-(U603-VSENSE)") (class "Default")
      (node (ref "R609") (pin "1") (pinfunction "1_1") (pintype "passive"))
      (node (ref "R611") (pin "2") (pinfunction "2_2") (pintype "passive"))
      (node (ref "U603") (pin "4") (pinfunction "VSENSE_4") (pintype "passive"))
    )
    (net (code "16") (name "VCC1V3") (class "Default")
      (node (ref "C614") (pin "2") (pinfunction "2_2") (pintype "passive"))
      (node (ref "C625") (pin "2") (pinfunction "2_2") (pintype "passive"))
      (node (ref "C626") (pin "2") (pinfunction "2_2") (pintype "passive"))
      (node (ref "C627") (pin "2") (pinfunction "2_2") (pintype "passive"))
      (node (ref "C628") (pin "2") (pinfunction "2_2") (pintype "passive"))
      (node (ref "C629") (pin "2") (pinfunction "2_2") (pintype "passive"))
      (node (ref "C630") (pin "2") (pinfunction "2_2") (pintype "passive"))
      (node (ref "C631") (pin "2") (pinfunction "2_2") (pintype "passive"))
      (node (ref "C632") (pin "2") (pinfunction "2_2") (pintype "passive"))
      (node (ref "C633") (pin "2") (pinfunction "2_2") (pintype "passive"))
      (node (ref "C634") (pin "2") (pinfunction "2_2") (pintype "passive"))
      (node (ref "C635") (pin "2") (pinfunction "2_2") (pintype "passive"))
      (node (ref "C636") (pin "2") (pinfunction "2_2") (pintype "passive"))
      (node (ref "R600") (pin "2") (pinfunction "2_2") (pintype "passive"))
      (node (ref "U1") (pin "100") (pinfunction "VDDINT_100") (pintype "passive"))
      (node (ref "U1") (pin "116") (pinfunction "VDDINT_116") (pintype "passive"))
      (node (ref "U1") (pin "138") (pinfunction "VDDINT_138") (pintype "passive"))
      (node (ref "U1") (pin "14") (pinfunction "VDDINT_14") (pintype "passive"))
      (node (ref "U1") (pin "152") (pinfunction "VDDINT_152") (pintype "passive"))
      (node (ref "U1") (pin "164") (pinfunction "VDDINT_164") (pintype "passive"))
      (node (ref "U1") (pin "23") (pinfunction "VDDINT_23") (pintype "passive"))
      (node (ref "U1") (pin "30") (pinfunction "VDDINT_30") (pintype "passive"))
      (node (ref "U1") (pin "63") (pinfunction "VDDINT_63") (pintype "passive"))
      (node (ref "U1") (pin "79") (pinfunction "VDDINT_79") (pintype "passive"))
      (node (ref "U1") (pin "98") (pinfunction "VDDINT_98") (pintype "passive"))
    )
    (net (code "17") (name "VCC3V3") (class "Default")
      (node (ref "C600") (pin "2") (pinfunction "2_2") (pintype "passive"))
      (node (ref "C601") (pin "2") (pinfunction "2_2") (pintype "passive"))
      (node (ref "C602") (pin "2") (pinfunction "2_2") (pintype "passive"))
      (node (ref "C603") (pin "2") (pinfunction "2_2") (pintype "passive"))
      (node (ref "C604") (pin "2") (pinfunction "2_2") (pintype "passive"))
      (node (ref "C605") (pin "2") (pinfunction "2_2") (pintype "passive"))
      (node (ref "C606") (pin "2") (pinfunction "2_2") (pintype "passive"))
      (node (ref "C607") (pin "2") (pinfunction "2_2") (pintype "passive"))
      (node (ref "C608") (pin "2") (pinfunction "2_2") (pintype "passive"))
      (node (ref "C609") (pin "2") (pinfunction "2_2") (pintype "passive"))
      (node (ref "C610") (pin "2") (pinfunction "2_2") (pintype "passive"))
      (node (ref "C611") (pin "2") (pinfunction "2_2") (pintype "passive"))
      (node (ref "C612") (pin "2") (pinfunction "2_2") (pintype "passive"))
      (node (ref "C613") (pin "2") (pinfunction "2_2") (pintype "passive"))
      (node (ref "C615") (pin "2") (pinfunction "2_2") (pintype "passive"))
      (node (ref "C616") (pin "2") (pinfunction "2_2") (pintype "passive"))
      (node (ref "C617") (pin "2") (pinfunction "2_2") (pintype "passive"))
      (node (ref "C618") (pin "2") (pinfunction "2_2") (pintype "passive"))
      (node (ref "C619") (pin "2") (pinfunction "2_2") (pintype "passive"))
      (node (ref "C620") (pin "2") (pinfunction "2_2") (pintype "passive"))
      (node (ref "C621") (pin "2") (pinfunction "2_2") (pintype "passive"))
      (node (ref "C622") (pin "2") (pinfunction "2_2") (pintype "passive"))
      (node (ref "C623") (pin "2") (pinfunction "2_2") (pintype "passive"))
      (node (ref "C624") (pin "2") (pinfunction "2_2") (pintype "passive"))
      (node (ref "C637") (pin "2") (pinfunction "2_2") (pintype "passive"))
      (node (ref "C638") (pin "2") (pinfunction "2_2") (pintype "passive"))
      (node (ref "C639") (pin "2") (pinfunction "2_2") (pintype "passive"))
      (node (ref "C640") (pin "2") (pinfunction "2_2") (pintype "passive"))
      (node (ref "C641") (pin "2") (pinfunction "2_2") (pintype "passive"))
      (node (ref "R601") (pin "2") (pinfunction "2_2") (pintype "passive"))
      (node (ref "R605") (pin "2") (pinfunction "2_2") (pintype "passive"))
      (node (ref "U1") (pin "104") (pinfunction "VDDMEM_104") (pintype "passive"))
      (node (ref "U1") (pin "112") (pinfunction "VDDMEM_112") (pintype "passive"))
      (node (ref "U1") (pin "124") (pinfunction "VDDMEM_124") (pintype "passive"))
      (node (ref "U1") (pin "126") (pinfunction "VDDFLASH_126") (pintype "passive"))
      (node (ref "U1") (pin "128") (pinfunction "VDDEXT_128") (pintype "passive"))
      (node (ref "U1") (pin "129") (pinfunction "VDDEXT_129") (pintype "passive"))
      (node (ref "U1") (pin "136") (pinfunction "VDDEXT_136") (pintype "passive"))
      (node (ref "U1") (pin "145") (pinfunction "VDDEXT_145") (pintype "passive"))
      (node (ref "U1") (pin "148") (pinfunction "VDDEXT_148") (pintype "passive"))
      (node (ref "U1") (pin "158") (pinfunction "VDDEXT_158") (pintype "passive"))
      (node (ref "U1") (pin "16") (pinfunction "VDDFLASH_16") (pintype "passive"))
      (node (ref "U1") (pin "17") (pinfunction "VDDFLASH_17") (pintype "passive"))
      (node (ref "U1") (pin "170") (pinfunction "VDDEXT_170") (pintype "passive"))
      (node (ref "U1") (pin "24") (pinfunction "VDDEXT_24") (pintype "passive"))
      (node (ref "U1") (pin "29") (pinfunction "VDDFLASH_29") (pintype "passive"))
      (node (ref "U1") (pin "35") (pinfunction "VDDEXT_35") (pintype "passive"))
      (node (ref "U1") (pin "49") (pinfunction "VDDEXT_49") (pintype "passive"))
      (node (ref "U1") (pin "59") (pinfunction "VDDMEM_59") (pintype "passive"))
      (node (ref "U1") (pin "68") (pinfunction "VDDMEM_68") (pintype "passive"))
      (node (ref "U1") (pin "7") (pinfunction "VDDEXT_7") (pintype "passive"))
      (node (ref "U1") (pin "75") (pinfunction "VDDMEM_75") (pintype "passive"))
      (node (ref "U1") (pin "82") (pinfunction "VDDMEM_82") (pintype "passive"))
      (node (ref "U1") (pin "95") (pinfunction "VDDMEM_95") (pintype "passive"))
      (node (ref "U601") (pin "1") (pinfunction "IN_1") (pintype "passive"))
    )
    (net (code "18") (name "VCC5V") (class "Default")
      (node (ref "R608") (pin "2") (pinfunction "2_2") (pintype "passive"))
    )
    (net (code "19") (name "VCC9V") (class "Default")
      (node (ref "C643") (pin "2") (pinfunction "2_2") (pintype "passive"))
      (node (ref "C644") (pin "2") (pinfunction "2_2") (pintype "passive"))
      (node (ref "C648") (pin "2") (pinfunction "2_2") (pintype "passive"))
      (node (ref "C649") (pin "2") (pinfunction "2_2") (pintype "passive"))
      (node (ref "D601") (pin "2") (pinfunction "K_2") (pintype "passive"))
      (node (ref "U602") (pin "7") (pinfunction "VIN_7") (pintype "passive"))
      (node (ref "U603") (pin "7") (pinfunction "VIN_7") (pintype "passive"))
    )
    (net (code "20") (name "unconnected-(U1D-VDDOTP-Pad9)") (class "Default")
      (node (ref "U1") (pin "9") (pinfunction "VDDOTP_9") (pintype "passive"))
    )
    (net (code "21") (name "unconnected-(U1D-VDDRTC-Pad142)") (class "Default")
      (node (ref "U1") (pin "142") (pinfunction "VDDRTC_142") (pintype "passive"))
    )
    (net (code "22") (name "unconnected-(U1D-VPPOTP-Pad8)") (class "Default")
      (node (ref "U1") (pin "8") (pinfunction "VPPOTP_8") (pintype "passive"))
    )
    (net (code "23") (name "unconnected-(U602-ENA-Pad5)") (class "Default")
      (node (ref "U602") (pin "5") (pinfunction "ENA_5") (pintype "passive+no_connect"))
    )
    (net (code "24") (name "unconnected-(U602-NC-Pad2)") (class "Default")
      (node (ref "U602") (pin "2") (pinfunction "NC_2") (pintype "passive+no_connect"))
    )
    (net (code "25") (name "unconnected-(U602-NC-Pad3)") (class "Default")
      (node (ref "U602") (pin "3") (pinfunction "NC_3") (pintype "passive+no_connect"))
    )
    (net (code "26") (name "unconnected-(U603-ENA-Pad5)") (class "Default")
      (node (ref "U603") (pin "5") (pinfunction "ENA_5") (pintype "passive+no_connect"))
    )
    (net (code "27") (name "unconnected-(U603-NC-Pad2)") (class "Default")
      (node (ref "U603") (pin "2") (pinfunction "NC_2") (pintype "passive+no_connect"))
    )
    (net (code "28") (name "unconnected-(U603-NC-Pad3)") (class "Default")
      (node (ref "U603") (pin "3") (pinfunction "NC_3") (pintype "passive+no_connect"))
    )
  )
)
